# 16.net
KiCad netlist of a schematic drawn in Altium Designer
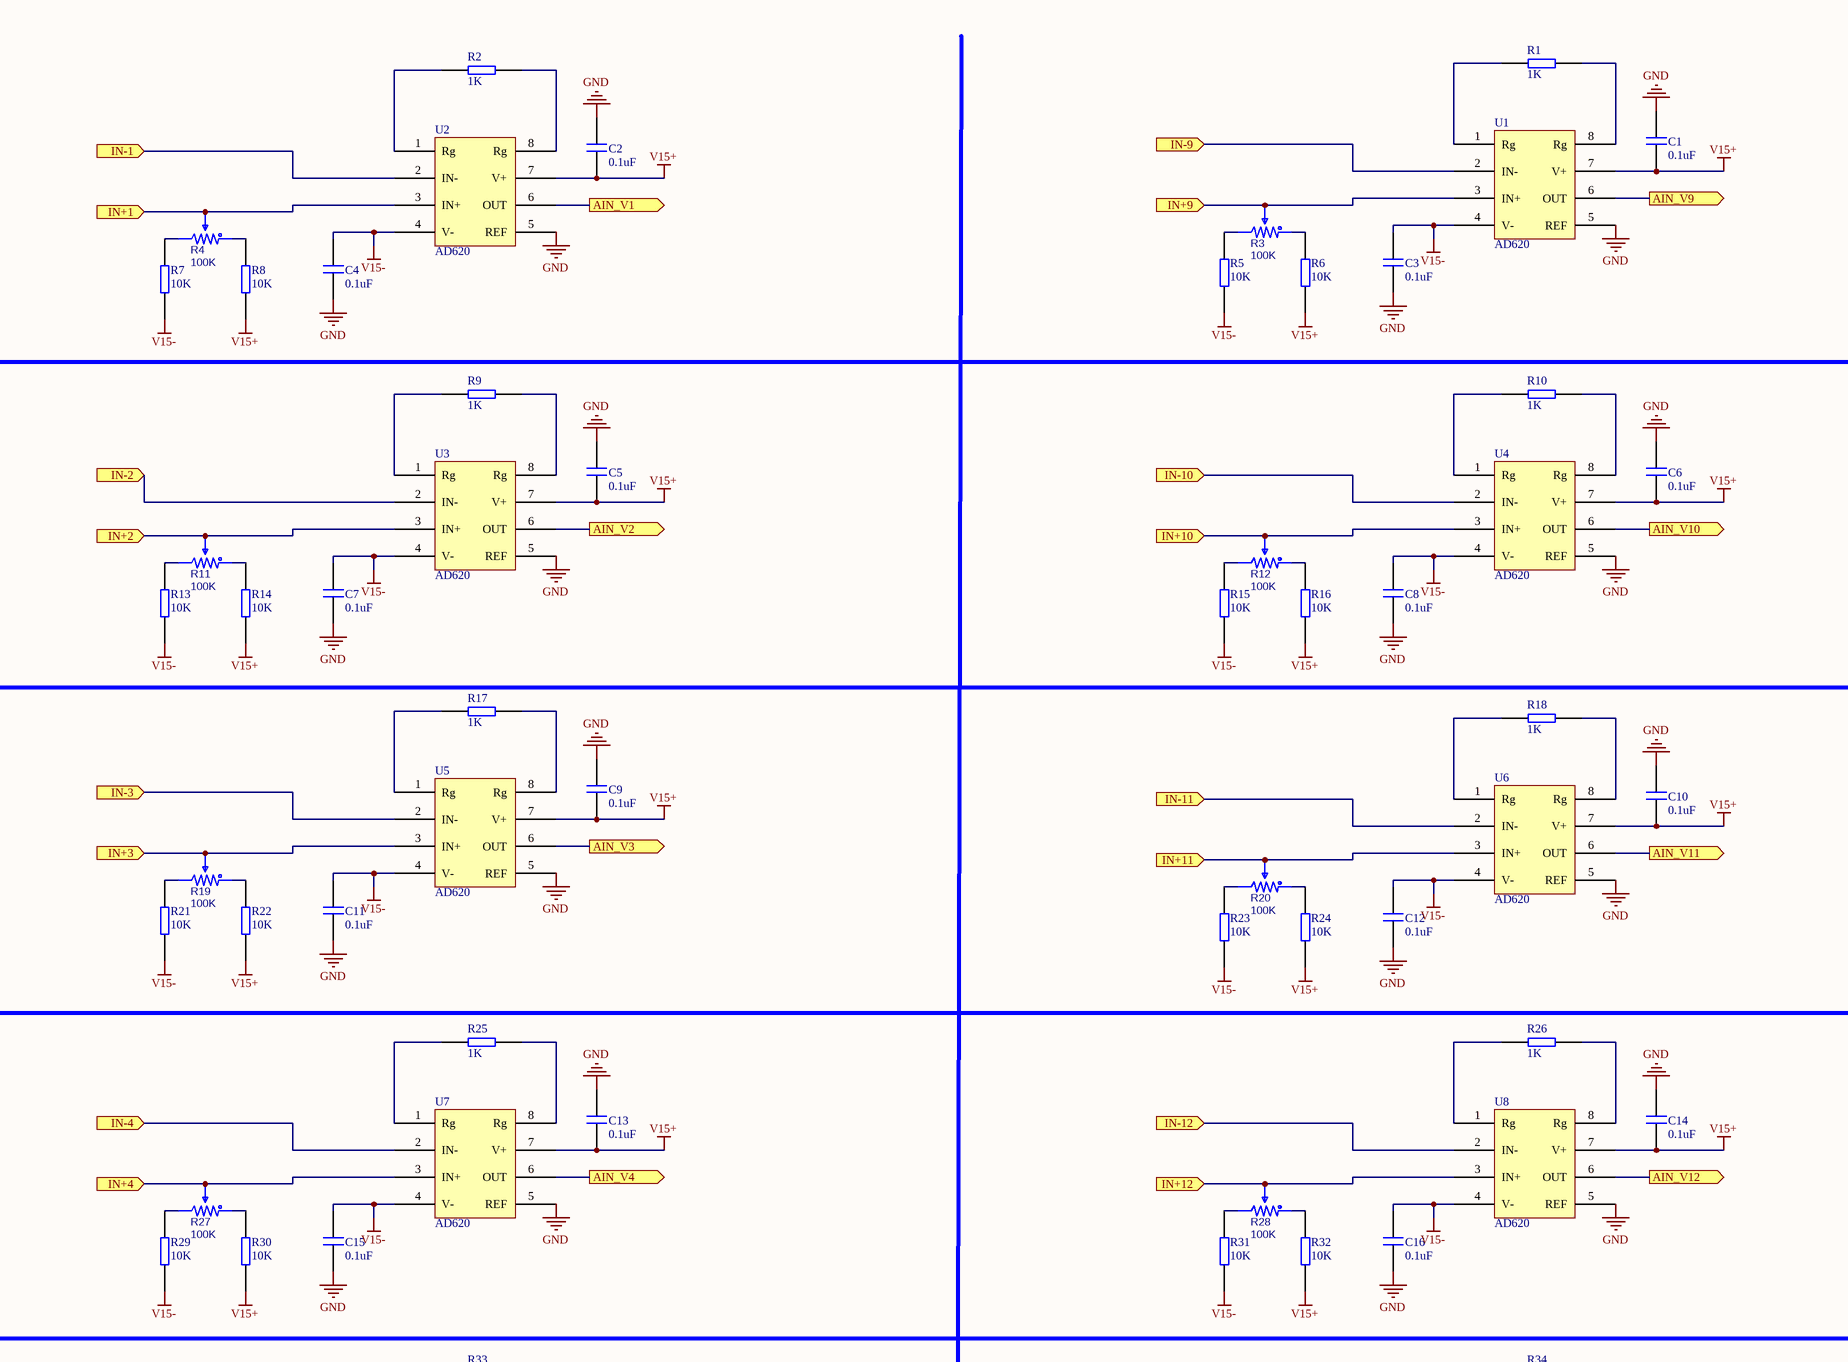
[diagram p0: 16路放大模块.SchDoc, top]
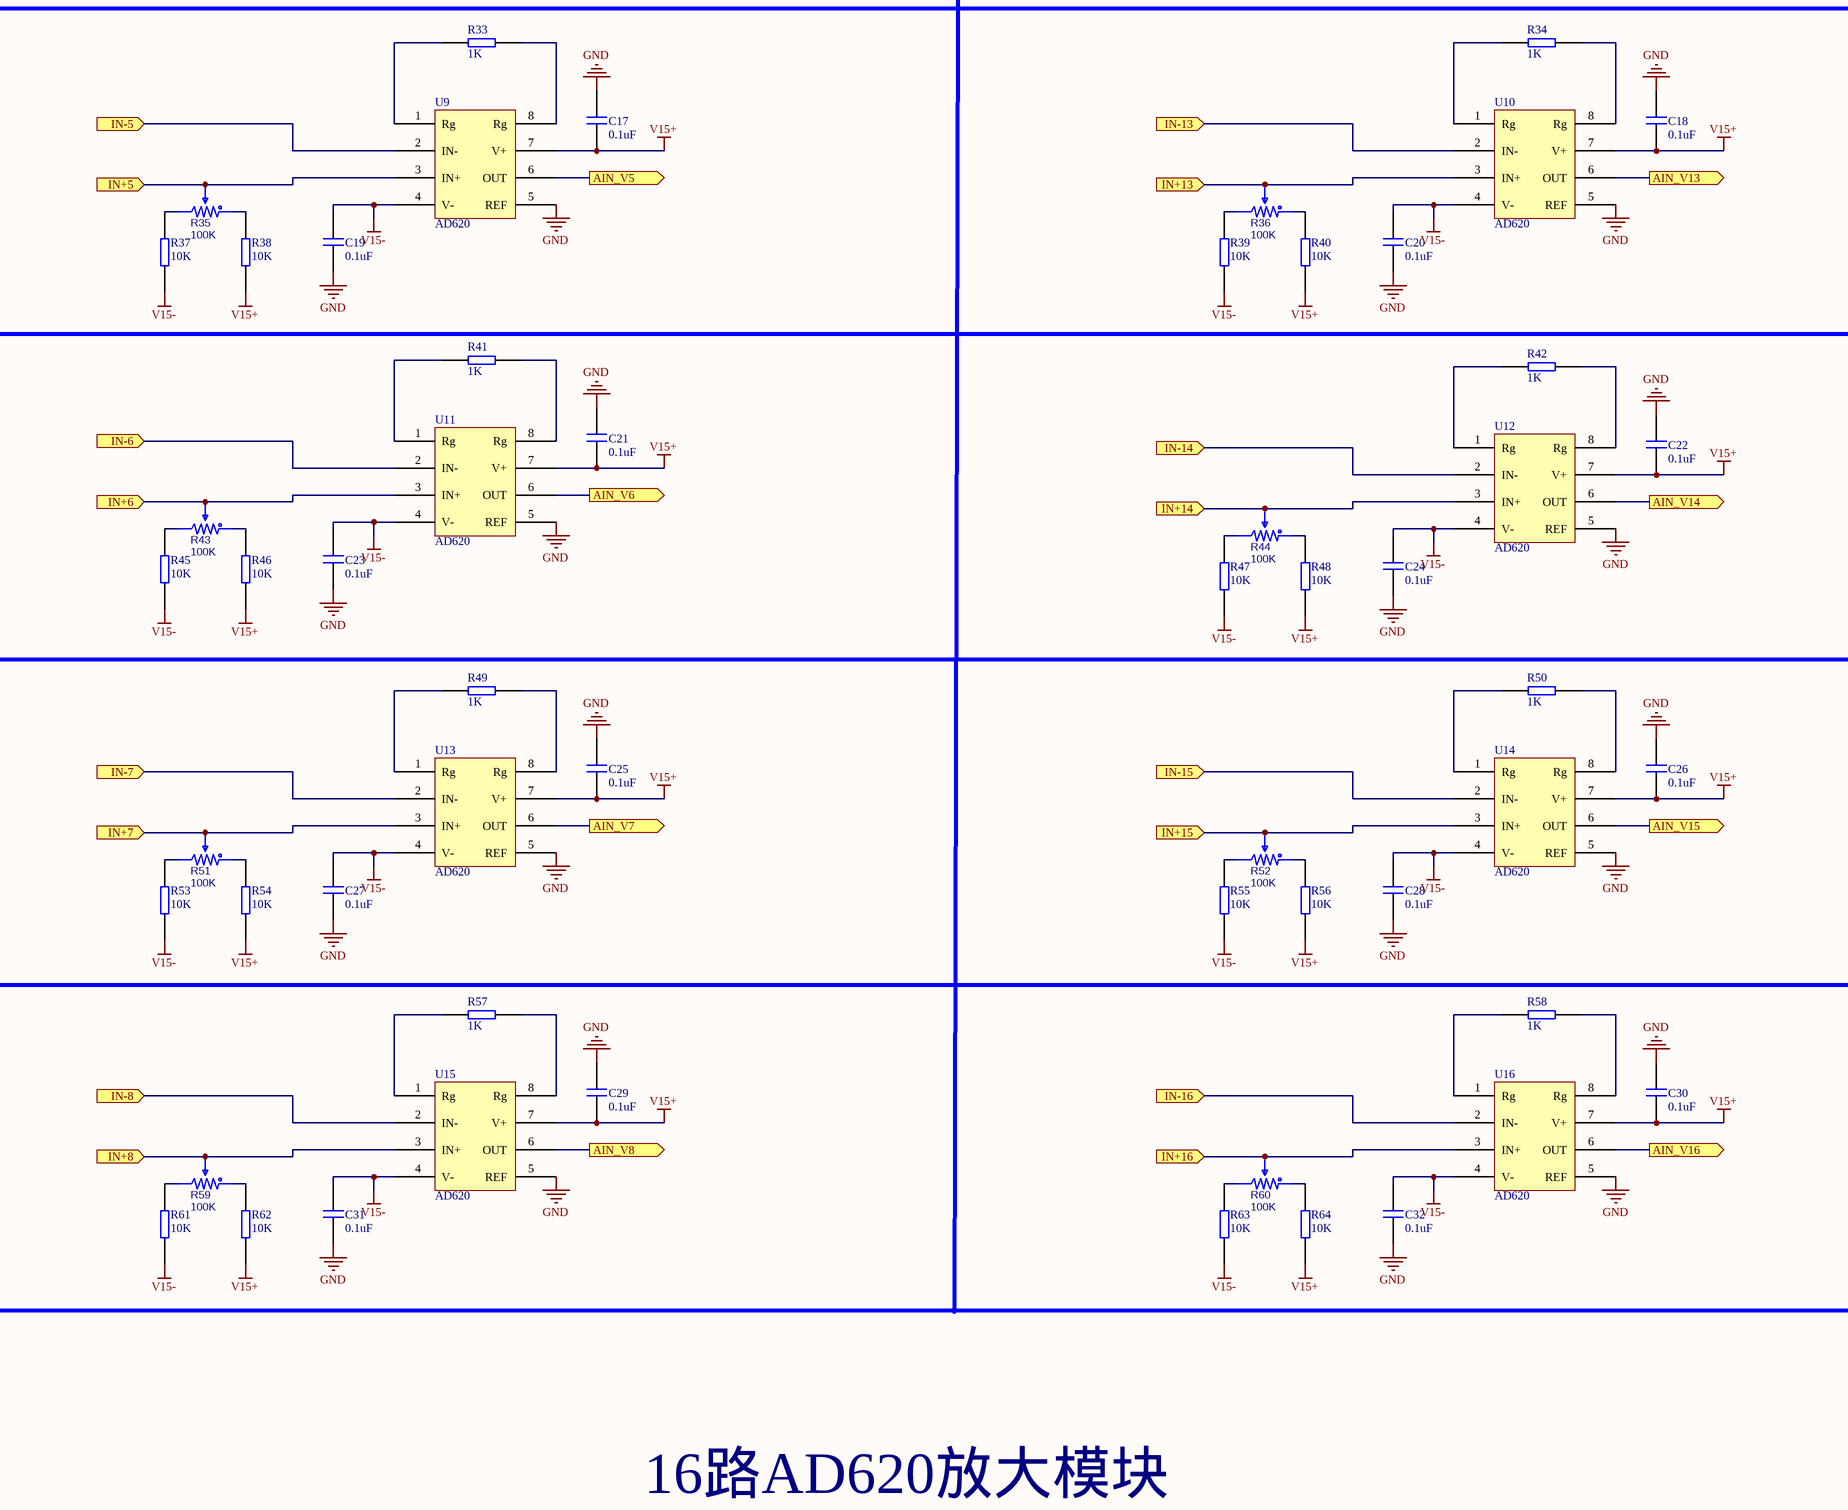
[diagram p1: 16路放大模块.SchDoc, bottom]

(export (version "E")
  (design (tool "Eeschema 10.0.6"))
  (components
    (comp (ref "C1")
      (value "0.1uF")
      (footprint "0805C")
      (description "普通电容")
      (libsource (lib "毕业设计") (part "CAP"))
    )
    (comp (ref "C2")
      (value "0.1uF")
      (footprint "0805C")
      (description "普通电容")
      (libsource (lib "毕业设计") (part "CAP"))
    )
    (comp (ref "C3")
      (value "0.1uF")
      (footprint "0805C")
      (description "普通电容")
      (libsource (lib "毕业设计") (part "CAP"))
    )
    (comp (ref "C4")
      (value "0.1uF")
      (footprint "0805C")
      (description "普通电容")
      (libsource (lib "毕业设计") (part "CAP"))
    )
    (comp (ref "C5")
      (value "0.1uF")
      (footprint "0805C")
      (description "普通电容")
      (libsource (lib "毕业设计") (part "CAP"))
    )
    (comp (ref "C6")
      (value "0.1uF")
      (footprint "0805C")
      (description "普通电容")
      (libsource (lib "毕业设计") (part "CAP"))
    )
    (comp (ref "C7")
      (value "0.1uF")
      (footprint "0805C")
      (description "普通电容")
      (libsource (lib "毕业设计") (part "CAP"))
    )
    (comp (ref "C8")
      (value "0.1uF")
      (footprint "0805C")
      (description "普通电容")
      (libsource (lib "毕业设计") (part "CAP"))
    )
    (comp (ref "C9")
      (value "0.1uF")
      (footprint "0805C")
      (description "普通电容")
      (libsource (lib "毕业设计") (part "CAP"))
    )
    (comp (ref "C10")
      (value "0.1uF")
      (footprint "0805C")
      (description "普通电容")
      (libsource (lib "毕业设计") (part "CAP"))
    )
    (comp (ref "C11")
      (value "0.1uF")
      (footprint "0805C")
      (description "普通电容")
      (libsource (lib "毕业设计") (part "CAP"))
    )
    (comp (ref "C12")
      (value "0.1uF")
      (footprint "0805C")
      (description "普通电容")
      (libsource (lib "毕业设计") (part "CAP"))
    )
    (comp (ref "C13")
      (value "0.1uF")
      (footprint "0805C")
      (description "普通电容")
      (libsource (lib "毕业设计") (part "CAP"))
    )
    (comp (ref "C14")
      (value "0.1uF")
      (footprint "0805C")
      (description "普通电容")
      (libsource (lib "毕业设计") (part "CAP"))
    )
    (comp (ref "C15")
      (value "0.1uF")
      (footprint "0805C")
      (description "普通电容")
      (libsource (lib "毕业设计") (part "CAP"))
    )
    (comp (ref "C16")
      (value "0.1uF")
      (footprint "0805C")
      (description "普通电容")
      (libsource (lib "毕业设计") (part "CAP"))
    )
    (comp (ref "C17")
      (value "0.1uF")
      (footprint "0805C")
      (description "普通电容")
      (libsource (lib "毕业设计") (part "CAP"))
    )
    (comp (ref "C18")
      (value "0.1uF")
      (footprint "0805C")
      (description "普通电容")
      (libsource (lib "毕业设计") (part "CAP"))
    )
    (comp (ref "C19")
      (value "0.1uF")
      (footprint "0805C")
      (description "普通电容")
      (libsource (lib "毕业设计") (part "CAP"))
    )
    (comp (ref "C20")
      (value "0.1uF")
      (footprint "0805C")
      (description "普通电容")
      (libsource (lib "毕业设计") (part "CAP"))
    )
    (comp (ref "C21")
      (value "0.1uF")
      (footprint "0805C")
      (description "普通电容")
      (libsource (lib "毕业设计") (part "CAP"))
    )
    (comp (ref "C22")
      (value "0.1uF")
      (footprint "0805C")
      (description "普通电容")
      (libsource (lib "毕业设计") (part "CAP"))
    )
    (comp (ref "C23")
      (value "0.1uF")
      (footprint "0805C")
      (description "普通电容")
      (libsource (lib "毕业设计") (part "CAP"))
    )
    (comp (ref "C24")
      (value "0.1uF")
      (footprint "0805C")
      (description "普通电容")
      (libsource (lib "毕业设计") (part "CAP"))
    )
    (comp (ref "C25")
      (value "0.1uF")
      (footprint "0805C")
      (description "普通电容")
      (libsource (lib "毕业设计") (part "CAP"))
    )
    (comp (ref "C26")
      (value "0.1uF")
      (footprint "0805C")
      (description "普通电容")
      (libsource (lib "毕业设计") (part "CAP"))
    )
    (comp (ref "C27")
      (value "0.1uF")
      (footprint "0805C")
      (description "普通电容")
      (libsource (lib "毕业设计") (part "CAP"))
    )
    (comp (ref "C28")
      (value "0.1uF")
      (footprint "0805C")
      (description "普通电容")
      (libsource (lib "毕业设计") (part "CAP"))
    )
    (comp (ref "C29")
      (value "0.1uF")
      (footprint "0805C")
      (description "普通电容")
      (libsource (lib "毕业设计") (part "CAP"))
    )
    (comp (ref "C30")
      (value "0.1uF")
      (footprint "0805C")
      (description "普通电容")
      (libsource (lib "毕业设计") (part "CAP"))
    )
    (comp (ref "C31")
      (value "0.1uF")
      (footprint "0805C")
      (description "普通电容")
      (libsource (lib "毕业设计") (part "CAP"))
    )
    (comp (ref "C32")
      (value "0.1uF")
      (footprint "0805C")
      (description "普通电容")
      (libsource (lib "毕业设计") (part "CAP"))
    )
    (comp (ref "R1")
      (value "1K")
      (footprint "0805R")
      (description "电阻模型")
      (libsource (lib "毕业设计") (part "RES"))
    )
    (comp (ref "R2")
      (value "1K")
      (footprint "0805R")
      (description "电阻模型")
      (libsource (lib "毕业设计") (part "RES"))
    )
    (comp (ref "R3")
      (value "100K")
      (footprint "RES-ADJ-SMD_G43BT")
      (description "电位器")
      (fields
        (field (name "BOM_SUPPLIER PART") "C125003")
        (field (name "BOM_MANUFACTURER PART") "3323P-1-104")
        (field (name "CONTRIBUTOR") "LCSC")
      )
      (libsource (lib "毕业设计") (part "100K"))
    )
    (comp (ref "R4")
      (value "100K")
      (footprint "RES-ADJ-SMD_G43BT")
      (description "电位器")
      (fields
        (field (name "BOM_SUPPLIER PART") "C125003")
        (field (name "BOM_MANUFACTURER PART") "3323P-1-104")
        (field (name "CONTRIBUTOR") "LCSC")
      )
      (libsource (lib "毕业设计") (part "100K"))
    )
    (comp (ref "R5")
      (value "10K")
      (footprint "0603R")
      (description "电阻模型")
      (libsource (lib "毕业设计") (part "RES"))
    )
    (comp (ref "R6")
      (value "10K")
      (footprint "0603R")
      (description "电阻模型")
      (libsource (lib "毕业设计") (part "RES"))
    )
    (comp (ref "R7")
      (value "10K")
      (footprint "0603R")
      (description "电阻模型")
      (libsource (lib "毕业设计") (part "RES"))
    )
    (comp (ref "R8")
      (value "10K")
      (footprint "0603R")
      (description "电阻模型")
      (libsource (lib "毕业设计") (part "RES"))
    )
    (comp (ref "R9")
      (value "1K")
      (footprint "0805R")
      (description "电阻模型")
      (libsource (lib "毕业设计") (part "RES"))
    )
    (comp (ref "R10")
      (value "1K")
      (footprint "0805R")
      (description "电阻模型")
      (libsource (lib "毕业设计") (part "RES"))
    )
    (comp (ref "R11")
      (value "100K")
      (footprint "RES-ADJ-SMD_G43BT")
      (description "电位器")
      (fields
        (field (name "BOM_SUPPLIER PART") "C125003")
        (field (name "BOM_MANUFACTURER PART") "3323P-1-104")
        (field (name "CONTRIBUTOR") "LCSC")
      )
      (libsource (lib "毕业设计") (part "100K"))
    )
    (comp (ref "R12")
      (value "100K")
      (footprint "RES-ADJ-SMD_G43BT")
      (description "电位器")
      (fields
        (field (name "BOM_SUPPLIER PART") "C125003")
        (field (name "BOM_MANUFACTURER PART") "3323P-1-104")
        (field (name "CONTRIBUTOR") "LCSC")
      )
      (libsource (lib "毕业设计") (part "100K"))
    )
    (comp (ref "R13")
      (value "10K")
      (footprint "0603R")
      (description "电阻模型")
      (libsource (lib "毕业设计") (part "RES"))
    )
    (comp (ref "R14")
      (value "10K")
      (footprint "0603R")
      (description "电阻模型")
      (libsource (lib "毕业设计") (part "RES"))
    )
    (comp (ref "R15")
      (value "10K")
      (footprint "0603R")
      (description "电阻模型")
      (libsource (lib "毕业设计") (part "RES"))
    )
    (comp (ref "R16")
      (value "10K")
      (footprint "0603R")
      (description "电阻模型")
      (libsource (lib "毕业设计") (part "RES"))
    )
    (comp (ref "R17")
      (value "1K")
      (footprint "0805R")
      (description "电阻模型")
      (libsource (lib "毕业设计") (part "RES"))
    )
    (comp (ref "R18")
      (value "1K")
      (footprint "0805R")
      (description "电阻模型")
      (libsource (lib "毕业设计") (part "RES"))
    )
    (comp (ref "R19")
      (value "100K")
      (footprint "RES-ADJ-SMD_G43BT")
      (description "电位器")
      (fields
        (field (name "BOM_SUPPLIER PART") "C125003")
        (field (name "BOM_MANUFACTURER PART") "3323P-1-104")
        (field (name "CONTRIBUTOR") "LCSC")
      )
      (libsource (lib "毕业设计") (part "100K"))
    )
    (comp (ref "R20")
      (value "100K")
      (footprint "RES-ADJ-SMD_G43BT")
      (description "电位器")
      (fields
        (field (name "BOM_SUPPLIER PART") "C125003")
        (field (name "BOM_MANUFACTURER PART") "3323P-1-104")
        (field (name "CONTRIBUTOR") "LCSC")
      )
      (libsource (lib "毕业设计") (part "100K"))
    )
    (comp (ref "R21")
      (value "10K")
      (footprint "0603R")
      (description "电阻模型")
      (libsource (lib "毕业设计") (part "RES"))
    )
    (comp (ref "R22")
      (value "10K")
      (footprint "0603R")
      (description "电阻模型")
      (libsource (lib "毕业设计") (part "RES"))
    )
    (comp (ref "R23")
      (value "10K")
      (footprint "0603R")
      (description "电阻模型")
      (libsource (lib "毕业设计") (part "RES"))
    )
    (comp (ref "R24")
      (value "10K")
      (footprint "0603R")
      (description "电阻模型")
      (libsource (lib "毕业设计") (part "RES"))
    )
    (comp (ref "R25")
      (value "1K")
      (footprint "0805R")
      (description "电阻模型")
      (libsource (lib "毕业设计") (part "RES"))
    )
    (comp (ref "R26")
      (value "1K")
      (footprint "0805R")
      (description "电阻模型")
      (libsource (lib "毕业设计") (part "RES"))
    )
    (comp (ref "R27")
      (value "100K")
      (footprint "RES-ADJ-SMD_G43BT")
      (description "电位器")
      (fields
        (field (name "BOM_SUPPLIER PART") "C125003")
        (field (name "BOM_MANUFACTURER PART") "3323P-1-104")
        (field (name "CONTRIBUTOR") "LCSC")
      )
      (libsource (lib "毕业设计") (part "100K"))
    )
    (comp (ref "R28")
      (value "100K")
      (footprint "RES-ADJ-SMD_G43BT")
      (description "电位器")
      (fields
        (field (name "BOM_SUPPLIER PART") "C125003")
        (field (name "BOM_MANUFACTURER PART") "3323P-1-104")
        (field (name "CONTRIBUTOR") "LCSC")
      )
      (libsource (lib "毕业设计") (part "100K"))
    )
    (comp (ref "R29")
      (value "10K")
      (footprint "0603R")
      (description "电阻模型")
      (libsource (lib "毕业设计") (part "RES"))
    )
    (comp (ref "R30")
      (value "10K")
      (footprint "0603R")
      (description "电阻模型")
      (libsource (lib "毕业设计") (part "RES"))
    )
    (comp (ref "R31")
      (value "10K")
      (footprint "0603R")
      (description "电阻模型")
      (libsource (lib "毕业设计") (part "RES"))
    )
    (comp (ref "R32")
      (value "10K")
      (footprint "0603R")
      (description "电阻模型")
      (libsource (lib "毕业设计") (part "RES"))
    )
    (comp (ref "R33")
      (value "1K")
      (footprint "0805R")
      (description "电阻模型")
      (libsource (lib "毕业设计") (part "RES"))
    )
    (comp (ref "R34")
      (value "1K")
      (footprint "0805R")
      (description "电阻模型")
      (libsource (lib "毕业设计") (part "RES"))
    )
    (comp (ref "R35")
      (value "100K")
      (footprint "RES-ADJ-SMD_G43BT")
      (description "电位器")
      (fields
        (field (name "BOM_SUPPLIER PART") "C125003")
        (field (name "BOM_MANUFACTURER PART") "3323P-1-104")
        (field (name "CONTRIBUTOR") "LCSC")
      )
      (libsource (lib "毕业设计") (part "100K"))
    )
    (comp (ref "R36")
      (value "100K")
      (footprint "RES-ADJ-SMD_G43BT")
      (description "电位器")
      (fields
        (field (name "BOM_SUPPLIER PART") "C125003")
        (field (name "BOM_MANUFACTURER PART") "3323P-1-104")
        (field (name "CONTRIBUTOR") "LCSC")
      )
      (libsource (lib "毕业设计") (part "100K"))
    )
    (comp (ref "R37")
      (value "10K")
      (footprint "0603R")
      (description "电阻模型")
      (libsource (lib "毕业设计") (part "RES"))
    )
    (comp (ref "R38")
      (value "10K")
      (footprint "0603R")
      (description "电阻模型")
      (libsource (lib "毕业设计") (part "RES"))
    )
    (comp (ref "R39")
      (value "10K")
      (footprint "0603R")
      (description "电阻模型")
      (libsource (lib "毕业设计") (part "RES"))
    )
    (comp (ref "R40")
      (value "10K")
      (footprint "0603R")
      (description "电阻模型")
      (libsource (lib "毕业设计") (part "RES"))
    )
    (comp (ref "R41")
      (value "1K")
      (footprint "0805R")
      (description "电阻模型")
      (libsource (lib "毕业设计") (part "RES"))
    )
    (comp (ref "R42")
      (value "1K")
      (footprint "0805R")
      (description "电阻模型")
      (libsource (lib "毕业设计") (part "RES"))
    )
    (comp (ref "R43")
      (value "100K")
      (footprint "RES-ADJ-SMD_G43BT")
      (description "电位器")
      (fields
        (field (name "BOM_SUPPLIER PART") "C125003")
        (field (name "BOM_MANUFACTURER PART") "3323P-1-104")
        (field (name "CONTRIBUTOR") "LCSC")
      )
      (libsource (lib "毕业设计") (part "100K"))
    )
    (comp (ref "R44")
      (value "100K")
      (footprint "RES-ADJ-SMD_G43BT")
      (description "电位器")
      (fields
        (field (name "BOM_SUPPLIER PART") "C125003")
        (field (name "BOM_MANUFACTURER PART") "3323P-1-104")
        (field (name "CONTRIBUTOR") "LCSC")
      )
      (libsource (lib "毕业设计") (part "100K"))
    )
    (comp (ref "R45")
      (value "10K")
      (footprint "0603R")
      (description "电阻模型")
      (libsource (lib "毕业设计") (part "RES"))
    )
    (comp (ref "R46")
      (value "10K")
      (footprint "0603R")
      (description "电阻模型")
      (libsource (lib "毕业设计") (part "RES"))
    )
    (comp (ref "R47")
      (value "10K")
      (footprint "0603R")
      (description "电阻模型")
      (libsource (lib "毕业设计") (part "RES"))
    )
    (comp (ref "R48")
      (value "10K")
      (footprint "0603R")
      (description "电阻模型")
      (libsource (lib "毕业设计") (part "RES"))
    )
    (comp (ref "R49")
      (value "1K")
      (footprint "0805R")
      (description "电阻模型")
      (libsource (lib "毕业设计") (part "RES"))
    )
    (comp (ref "R50")
      (value "1K")
      (footprint "0805R")
      (description "电阻模型")
      (libsource (lib "毕业设计") (part "RES"))
    )
    (comp (ref "R51")
      (value "100K")
      (footprint "RES-ADJ-SMD_G43BT")
      (description "电位器")
      (fields
        (field (name "BOM_SUPPLIER PART") "C125003")
        (field (name "BOM_MANUFACTURER PART") "3323P-1-104")
        (field (name "CONTRIBUTOR") "LCSC")
      )
      (libsource (lib "毕业设计") (part "100K"))
    )
    (comp (ref "R52")
      (value "100K")
      (footprint "RES-ADJ-SMD_G43BT")
      (description "电位器")
      (fields
        (field (name "BOM_SUPPLIER PART") "C125003")
        (field (name "BOM_MANUFACTURER PART") "3323P-1-104")
        (field (name "CONTRIBUTOR") "LCSC")
      )
      (libsource (lib "毕业设计") (part "100K"))
    )
    (comp (ref "R53")
      (value "10K")
      (footprint "0603R")
      (description "电阻模型")
      (libsource (lib "毕业设计") (part "RES"))
    )
    (comp (ref "R54")
      (value "10K")
      (footprint "0603R")
      (description "电阻模型")
      (libsource (lib "毕业设计") (part "RES"))
    )
    (comp (ref "R55")
      (value "10K")
      (footprint "0603R")
      (description "电阻模型")
      (libsource (lib "毕业设计") (part "RES"))
    )
    (comp (ref "R56")
      (value "10K")
      (footprint "0603R")
      (description "电阻模型")
      (libsource (lib "毕业设计") (part "RES"))
    )
    (comp (ref "R57")
      (value "1K")
      (footprint "0805R")
      (description "电阻模型")
      (libsource (lib "毕业设计") (part "RES"))
    )
    (comp (ref "R58")
      (value "1K")
      (footprint "0805R")
      (description "电阻模型")
      (libsource (lib "毕业设计") (part "RES"))
    )
    (comp (ref "R59")
      (value "100K")
      (footprint "RES-ADJ-SMD_G43BT")
      (description "电位器")
      (fields
        (field (name "BOM_SUPPLIER PART") "C125003")
        (field (name "BOM_MANUFACTURER PART") "3323P-1-104")
        (field (name "CONTRIBUTOR") "LCSC")
      )
      (libsource (lib "毕业设计") (part "100K"))
    )
    (comp (ref "R60")
      (value "100K")
      (footprint "RES-ADJ-SMD_G43BT")
      (description "电位器")
      (fields
        (field (name "BOM_SUPPLIER PART") "C125003")
        (field (name "BOM_MANUFACTURER PART") "3323P-1-104")
        (field (name "CONTRIBUTOR") "LCSC")
      )
      (libsource (lib "毕业设计") (part "100K"))
    )
    (comp (ref "R61")
      (value "10K")
      (footprint "0603R")
      (description "电阻模型")
      (libsource (lib "毕业设计") (part "RES"))
    )
    (comp (ref "R62")
      (value "10K")
      (footprint "0603R")
      (description "电阻模型")
      (libsource (lib "毕业设计") (part "RES"))
    )
    (comp (ref "R63")
      (value "10K")
      (footprint "0603R")
      (description "电阻模型")
      (libsource (lib "毕业设计") (part "RES"))
    )
    (comp (ref "R64")
      (value "10K")
      (footprint "0603R")
      (description "电阻模型")
      (libsource (lib "毕业设计") (part "RES"))
    )
    (comp (ref "U1")
      (value "AD620")
      (footprint "SOIC127P600X175-8N")
      (description "仪表放大芯片")
      (libsource (lib "毕业设计") (part "AD620"))
    )
    (comp (ref "U2")
      (value "AD620")
      (footprint "SOIC127P600X175-8N")
      (description "仪表放大芯片")
      (libsource (lib "毕业设计") (part "AD620"))
    )
    (comp (ref "U3")
      (value "AD620")
      (footprint "SOIC127P600X175-8N")
      (description "仪表放大芯片")
      (libsource (lib "毕业设计") (part "AD620"))
    )
    (comp (ref "U4")
      (value "AD620")
      (footprint "SOIC127P600X175-8N")
      (description "仪表放大芯片")
      (libsource (lib "毕业设计") (part "AD620"))
    )
    (comp (ref "U5")
      (value "AD620")
      (footprint "SOIC127P600X175-8N")
      (description "仪表放大芯片")
      (libsource (lib "毕业设计") (part "AD620"))
    )
    (comp (ref "U6")
      (value "AD620")
      (footprint "SOIC127P600X175-8N")
      (description "仪表放大芯片")
      (libsource (lib "毕业设计") (part "AD620"))
    )
    (comp (ref "U7")
      (value "AD620")
      (footprint "SOIC127P600X175-8N")
      (description "仪表放大芯片")
      (libsource (lib "毕业设计") (part "AD620"))
    )
    (comp (ref "U8")
      (value "AD620")
      (footprint "SOIC127P600X175-8N")
      (description "仪表放大芯片")
      (libsource (lib "毕业设计") (part "AD620"))
    )
    (comp (ref "U9")
      (value "AD620")
      (footprint "SOIC127P600X175-8N")
      (description "仪表放大芯片")
      (libsource (lib "毕业设计") (part "AD620"))
    )
    (comp (ref "U10")
      (value "AD620")
      (footprint "SOIC127P600X175-8N")
      (description "仪表放大芯片")
      (libsource (lib "毕业设计") (part "AD620"))
    )
    (comp (ref "U11")
      (value "AD620")
      (footprint "SOIC127P600X175-8N")
      (description "仪表放大芯片")
      (libsource (lib "毕业设计") (part "AD620"))
    )
    (comp (ref "U12")
      (value "AD620")
      (footprint "SOIC127P600X175-8N")
      (description "仪表放大芯片")
      (libsource (lib "毕业设计") (part "AD620"))
    )
    (comp (ref "U13")
      (value "AD620")
      (footprint "SOIC127P600X175-8N")
      (description "仪表放大芯片")
      (libsource (lib "毕业设计") (part "AD620"))
    )
    (comp (ref "U14")
      (value "AD620")
      (footprint "SOIC127P600X175-8N")
      (description "仪表放大芯片")
      (libsource (lib "毕业设计") (part "AD620"))
    )
    (comp (ref "U15")
      (value "AD620")
      (footprint "SOIC127P600X175-8N")
      (description "仪表放大芯片")
      (libsource (lib "毕业设计") (part "AD620"))
    )
    (comp (ref "U16")
      (value "AD620")
      (footprint "SOIC127P600X175-8N")
      (description "仪表放大芯片")
      (libsource (lib "毕业设计") (part "AD620"))
    )
  )
  (nets
    (net (code "1") (name "/AIN_V1") (class "Default")
      (node (ref "U2") (pin "6") (pinfunction "OUT_6") (pintype "passive"))
    )
    (net (code "2") (name "/AIN_V2") (class "Default")
      (node (ref "U3") (pin "6") (pinfunction "OUT_6") (pintype "passive"))
    )
    (net (code "3") (name "/AIN_V3") (class "Default")
      (node (ref "U5") (pin "6") (pinfunction "OUT_6") (pintype "passive"))
    )
    (net (code "4") (name "/AIN_V4") (class "Default")
      (node (ref "U7") (pin "6") (pinfunction "OUT_6") (pintype "passive"))
    )
    (net (code "5") (name "/AIN_V5") (class "Default")
      (node (ref "U9") (pin "6") (pinfunction "OUT_6") (pintype "passive"))
    )
    (net (code "6") (name "/AIN_V6") (class "Default")
      (node (ref "U11") (pin "6") (pinfunction "OUT_6") (pintype "passive"))
    )
    (net (code "7") (name "/AIN_V7") (class "Default")
      (node (ref "U13") (pin "6") (pinfunction "OUT_6") (pintype "passive"))
    )
    (net (code "8") (name "/AIN_V8") (class "Default")
      (node (ref "U15") (pin "6") (pinfunction "OUT_6") (pintype "passive"))
    )
    (net (code "9") (name "/AIN_V9") (class "Default")
      (node (ref "U1") (pin "6") (pinfunction "OUT_6") (pintype "passive"))
    )
    (net (code "10") (name "/AIN_V10") (class "Default")
      (node (ref "U4") (pin "6") (pinfunction "OUT_6") (pintype "passive"))
    )
    (net (code "11") (name "/AIN_V11") (class "Default")
      (node (ref "U6") (pin "6") (pinfunction "OUT_6") (pintype "passive"))
    )
    (net (code "12") (name "/AIN_V12") (class "Default")
      (node (ref "U8") (pin "6") (pinfunction "OUT_6") (pintype "passive"))
    )
    (net (code "13") (name "/AIN_V13") (class "Default")
      (node (ref "U10") (pin "6") (pinfunction "OUT_6") (pintype "passive"))
    )
    (net (code "14") (name "/AIN_V14") (class "Default")
      (node (ref "U12") (pin "6") (pinfunction "OUT_6") (pintype "passive"))
    )
    (net (code "15") (name "/AIN_V15") (class "Default")
      (node (ref "U14") (pin "6") (pinfunction "OUT_6") (pintype "passive"))
    )
    (net (code "16") (name "/AIN_V16") (class "Default")
      (node (ref "U16") (pin "6") (pinfunction "OUT_6") (pintype "passive"))
    )
    (net (code "17") (name "/IN+1") (class "Default")
      (node (ref "R4") (pin "2") (pinfunction "2_2") (pintype "passive"))
      (node (ref "U2") (pin "3") (pinfunction "IN+_3") (pintype "passive"))
    )
    (net (code "18") (name "/IN+2") (class "Default")
      (node (ref "R11") (pin "2") (pinfunction "2_2") (pintype "passive"))
      (node (ref "U3") (pin "3") (pinfunction "IN+_3") (pintype "passive"))
    )
    (net (code "19") (name "/IN+3") (class "Default")
      (node (ref "R19") (pin "2") (pinfunction "2_2") (pintype "passive"))
      (node (ref "U5") (pin "3") (pinfunction "IN+_3") (pintype "passive"))
    )
    (net (code "20") (name "/IN+4") (class "Default")
      (node (ref "R27") (pin "2") (pinfunction "2_2") (pintype "passive"))
      (node (ref "U7") (pin "3") (pinfunction "IN+_3") (pintype "passive"))
    )
    (net (code "21") (name "/IN+5") (class "Default")
      (node (ref "R35") (pin "2") (pinfunction "2_2") (pintype "passive"))
      (node (ref "U9") (pin "3") (pinfunction "IN+_3") (pintype "passive"))
    )
    (net (code "22") (name "/IN+6") (class "Default")
      (node (ref "R43") (pin "2") (pinfunction "2_2") (pintype "passive"))
      (node (ref "U11") (pin "3") (pinfunction "IN+_3") (pintype "passive"))
    )
    (net (code "23") (name "/IN+7") (class "Default")
      (node (ref "R51") (pin "2") (pinfunction "2_2") (pintype "passive"))
      (node (ref "U13") (pin "3") (pinfunction "IN+_3") (pintype "passive"))
    )
    (net (code "24") (name "/IN+8") (class "Default")
      (node (ref "R59") (pin "2") (pinfunction "2_2") (pintype "passive"))
      (node (ref "U15") (pin "3") (pinfunction "IN+_3") (pintype "passive"))
    )
    (net (code "25") (name "/IN+9") (class "Default")
      (node (ref "R3") (pin "2") (pinfunction "2_2") (pintype "passive"))
      (node (ref "U1") (pin "3") (pinfunction "IN+_3") (pintype "passive"))
    )
    (net (code "26") (name "/IN+10") (class "Default")
      (node (ref "R12") (pin "2") (pinfunction "2_2") (pintype "passive"))
      (node (ref "U4") (pin "3") (pinfunction "IN+_3") (pintype "passive"))
    )
    (net (code "27") (name "/IN+11") (class "Default")
      (node (ref "R20") (pin "2") (pinfunction "2_2") (pintype "passive"))
      (node (ref "U6") (pin "3") (pinfunction "IN+_3") (pintype "passive"))
    )
    (net (code "28") (name "/IN+12") (class "Default")
      (node (ref "R28") (pin "2") (pinfunction "2_2") (pintype "passive"))
      (node (ref "U8") (pin "3") (pinfunction "IN+_3") (pintype "passive"))
    )
    (net (code "29") (name "/IN+13") (class "Default")
      (node (ref "R36") (pin "2") (pinfunction "2_2") (pintype "passive"))
      (node (ref "U10") (pin "3") (pinfunction "IN+_3") (pintype "passive"))
    )
    (net (code "30") (name "/IN+14") (class "Default")
      (node (ref "R44") (pin "2") (pinfunction "2_2") (pintype "passive"))
      (node (ref "U12") (pin "3") (pinfunction "IN+_3") (pintype "passive"))
    )
    (net (code "31") (name "/IN+15") (class "Default")
      (node (ref "R52") (pin "2") (pinfunction "2_2") (pintype "passive"))
      (node (ref "U14") (pin "3") (pinfunction "IN+_3") (pintype "passive"))
    )
    (net (code "32") (name "/IN+16") (class "Default")
      (node (ref "R60") (pin "2") (pinfunction "2_2") (pintype "passive"))
      (node (ref "U16") (pin "3") (pinfunction "IN+_3") (pintype "passive"))
    )
    (net (code "33") (name "/IN-1") (class "Default")
      (node (ref "U2") (pin "2") (pinfunction "IN-_2") (pintype "passive"))
    )
    (net (code "34") (name "/IN-2") (class "Default")
      (node (ref "U3") (pin "2") (pinfunction "IN-_2") (pintype "passive"))
    )
    (net (code "35") (name "/IN-3") (class "Default")
      (node (ref "U5") (pin "2") (pinfunction "IN-_2") (pintype "passive"))
    )
    (net (code "36") (name "/IN-4") (class "Default")
      (node (ref "U7") (pin "2") (pinfunction "IN-_2") (pintype "passive"))
    )
    (net (code "37") (name "/IN-5") (class "Default")
      (node (ref "U9") (pin "2") (pinfunction "IN-_2") (pintype "passive"))
    )
    (net (code "38") (name "/IN-6") (class "Default")
      (node (ref "U11") (pin "2") (pinfunction "IN-_2") (pintype "passive"))
    )
    (net (code "39") (name "/IN-7") (class "Default")
      (node (ref "U13") (pin "2") (pinfunction "IN-_2") (pintype "passive"))
    )
    (net (code "40") (name "/IN-8") (class "Default")
      (node (ref "U15") (pin "2") (pinfunction "IN-_2") (pintype "passive"))
    )
    (net (code "41") (name "/IN-9") (class "Default")
      (node (ref "U1") (pin "2") (pinfunction "IN-_2") (pintype "passive"))
    )
    (net (code "42") (name "/IN-10") (class "Default")
      (node (ref "U4") (pin "2") (pinfunction "IN-_2") (pintype "passive"))
    )
    (net (code "43") (name "/IN-11") (class "Default")
      (node (ref "U6") (pin "2") (pinfunction "IN-_2") (pintype "passive"))
    )
    (net (code "44") (name "/IN-12") (class "Default")
      (node (ref "U8") (pin "2") (pinfunction "IN-_2") (pintype "passive"))
    )
    (net (code "45") (name "/IN-13") (class "Default")
      (node (ref "U10") (pin "2") (pinfunction "IN-_2") (pintype "passive"))
    )
    (net (code "46") (name "/IN-14") (class "Default")
      (node (ref "U12") (pin "2") (pinfunction "IN-_2") (pintype "passive"))
    )
    (net (code "47") (name "/IN-15") (class "Default")
      (node (ref "U14") (pin "2") (pinfunction "IN-_2") (pintype "passive"))
    )
    (net (code "48") (name "/IN-16") (class "Default")
      (node (ref "U16") (pin "2") (pinfunction "IN-_2") (pintype "passive"))
    )
    (net (code "49") (name "GND") (class "Default")
      (node (ref "C1") (pin "2") (pinfunction "2_2") (pintype "passive"))
      (node (ref "C10") (pin "2") (pinfunction "2_2") (pintype "passive"))
      (node (ref "C11") (pin "1") (pinfunction "1_1") (pintype "passive"))
      (node (ref "C12") (pin "1") (pinfunction "1_1") (pintype "passive"))
      (node (ref "C13") (pin "2") (pinfunction "2_2") (pintype "passive"))
      (node (ref "C14") (pin "2") (pinfunction "2_2") (pintype "passive"))
      (node (ref "C15") (pin "1") (pinfunction "1_1") (pintype "passive"))
      (node (ref "C16") (pin "1") (pinfunction "1_1") (pintype "passive"))
      (node (ref "C17") (pin "2") (pinfunction "2_2") (pintype "passive"))
      (node (ref "C18") (pin "2") (pinfunction "2_2") (pintype "passive"))
      (node (ref "C19") (pin "1") (pinfunction "1_1") (pintype "passive"))
      (node (ref "C2") (pin "2") (pinfunction "2_2") (pintype "passive"))
      (node (ref "C20") (pin "1") (pinfunction "1_1") (pintype "passive"))
      (node (ref "C21") (pin "2") (pinfunction "2_2") (pintype "passive"))
      (node (ref "C22") (pin "2") (pinfunction "2_2") (pintype "passive"))
      (node (ref "C23") (pin "1") (pinfunction "1_1") (pintype "passive"))
      (node (ref "C24") (pin "1") (pinfunction "1_1") (pintype "passive"))
      (node (ref "C25") (pin "2") (pinfunction "2_2") (pintype "passive"))
      (node (ref "C26") (pin "2") (pinfunction "2_2") (pintype "passive"))
      (node (ref "C27") (pin "1") (pinfunction "1_1") (pintype "passive"))
      (node (ref "C28") (pin "1") (pinfunction "1_1") (pintype "passive"))
      (node (ref "C29") (pin "2") (pinfunction "2_2") (pintype "passive"))
      (node (ref "C3") (pin "1") (pinfunction "1_1") (pintype "passive"))
      (node (ref "C30") (pin "2") (pinfunction "2_2") (pintype "passive"))
      (node (ref "C31") (pin "1") (pinfunction "1_1") (pintype "passive"))
      (node (ref "C32") (pin "1") (pinfunction "1_1") (pintype "passive"))
      (node (ref "C4") (pin "1") (pinfunction "1_1") (pintype "passive"))
      (node (ref "C5") (pin "2") (pinfunction "2_2") (pintype "passive"))
      (node (ref "C6") (pin "2") (pinfunction "2_2") (pintype "passive"))
      (node (ref "C7") (pin "1") (pinfunction "1_1") (pintype "passive"))
      (node (ref "C8") (pin "1") (pinfunction "1_1") (pintype "passive"))
      (node (ref "C9") (pin "2") (pinfunction "2_2") (pintype "passive"))
      (node (ref "U1") (pin "5") (pinfunction "REF_5") (pintype "passive"))
      (node (ref "U10") (pin "5") (pinfunction "REF_5") (pintype "passive"))
      (node (ref "U11") (pin "5") (pinfunction "REF_5") (pintype "passive"))
      (node (ref "U12") (pin "5") (pinfunction "REF_5") (pintype "passive"))
      (node (ref "U13") (pin "5") (pinfunction "REF_5") (pintype "passive"))
      (node (ref "U14") (pin "5") (pinfunction "REF_5") (pintype "passive"))
      (node (ref "U15") (pin "5") (pinfunction "REF_5") (pintype "passive"))
      (node (ref "U16") (pin "5") (pinfunction "REF_5") (pintype "passive"))
      (node (ref "U2") (pin "5") (pinfunction "REF_5") (pintype "passive"))
      (node (ref "U3") (pin "5") (pinfunction "REF_5") (pintype "passive"))
      (node (ref "U4") (pin "5") (pinfunction "REF_5") (pintype "passive"))
      (node (ref "U5") (pin "5") (pinfunction "REF_5") (pintype "passive"))
      (node (ref "U6") (pin "5") (pinfunction "REF_5") (pintype "passive"))
      (node (ref "U7") (pin "5") (pinfunction "REF_5") (pintype "passive"))
      (node (ref "U8") (pin "5") (pinfunction "REF_5") (pintype "passive"))
      (node (ref "U9") (pin "5") (pinfunction "REF_5") (pintype "passive"))
    )
    (net (code "50") (name "Net-(R1-Pad1)") (class "Default")
      (node (ref "R1") (pin "1") (pinfunction "1_1") (pintype "passive"))
      (node (ref "U1") (pin "1") (pinfunction "Rg_1") (pintype "passive"))
    )
    (net (code "51") (name "Net-(R1-Pad2)") (class "Default")
      (node (ref "R1") (pin "2") (pinfunction "2_2") (pintype "passive"))
      (node (ref "U1") (pin "8") (pinfunction "Rg_8") (pintype "passive"))
    )
    (net (code "52") (name "Net-(R2-Pad1)") (class "Default")
      (node (ref "R2") (pin "1") (pinfunction "1_1") (pintype "passive"))
      (node (ref "U2") (pin "1") (pinfunction "Rg_1") (pintype "passive"))
    )
    (net (code "53") (name "Net-(R2-Pad2)") (class "Default")
      (node (ref "R2") (pin "2") (pinfunction "2_2") (pintype "passive"))
      (node (ref "U2") (pin "8") (pinfunction "Rg_8") (pintype "passive"))
    )
    (net (code "54") (name "Net-(R3-Pad1)") (class "Default")
      (node (ref "R3") (pin "1") (pinfunction "1_1") (pintype "passive"))
      (node (ref "R6") (pin "2") (pinfunction "2_2") (pintype "passive"))
    )
    (net (code "55") (name "Net-(R3-Pad3)") (class "Default")
      (node (ref "R3") (pin "3") (pinfunction "3_3") (pintype "passive"))
      (node (ref "R5") (pin "2") (pinfunction "2_2") (pintype "passive"))
    )
    (net (code "56") (name "Net-(R4-Pad1)") (class "Default")
      (node (ref "R4") (pin "1") (pinfunction "1_1") (pintype "passive"))
      (node (ref "R8") (pin "2") (pinfunction "2_2") (pintype "passive"))
    )
    (net (code "57") (name "Net-(R4-Pad3)") (class "Default")
      (node (ref "R4") (pin "3") (pinfunction "3_3") (pintype "passive"))
      (node (ref "R7") (pin "2") (pinfunction "2_2") (pintype "passive"))
    )
    (net (code "58") (name "Net-(R9-Pad1)") (class "Default")
      (node (ref "R9") (pin "1") (pinfunction "1_1") (pintype "passive"))
      (node (ref "U3") (pin "1") (pinfunction "Rg_1") (pintype "passive"))
    )
    (net (code "59") (name "Net-(R9-Pad2)") (class "Default")
      (node (ref "R9") (pin "2") (pinfunction "2_2") (pintype "passive"))
      (node (ref "U3") (pin "8") (pinfunction "Rg_8") (pintype "passive"))
    )
    (net (code "60") (name "Net-(R10-Pad1)") (class "Default")
      (node (ref "R10") (pin "1") (pinfunction "1_1") (pintype "passive"))
      (node (ref "U4") (pin "1") (pinfunction "Rg_1") (pintype "passive"))
    )
    (net (code "61") (name "Net-(R10-Pad2)") (class "Default")
      (node (ref "R10") (pin "2") (pinfunction "2_2") (pintype "passive"))
      (node (ref "U4") (pin "8") (pinfunction "Rg_8") (pintype "passive"))
    )
    (net (code "62") (name "Net-(R11-Pad1)") (class "Default")
      (node (ref "R11") (pin "1") (pinfunction "1_1") (pintype "passive"))
      (node (ref "R14") (pin "2") (pinfunction "2_2") (pintype "passive"))
    )
    (net (code "63") (name "Net-(R11-Pad3)") (class "Default")
      (node (ref "R11") (pin "3") (pinfunction "3_3") (pintype "passive"))
      (node (ref "R13") (pin "2") (pinfunction "2_2") (pintype "passive"))
    )
    (net (code "64") (name "Net-(R12-Pad1)") (class "Default")
      (node (ref "R12") (pin "1") (pinfunction "1_1") (pintype "passive"))
      (node (ref "R16") (pin "2") (pinfunction "2_2") (pintype "passive"))
    )
    (net (code "65") (name "Net-(R12-Pad3)") (class "Default")
      (node (ref "R12") (pin "3") (pinfunction "3_3") (pintype "passive"))
      (node (ref "R15") (pin "2") (pinfunction "2_2") (pintype "passive"))
    )
    (net (code "66") (name "Net-(R17-Pad1)") (class "Default")
      (node (ref "R17") (pin "1") (pinfunction "1_1") (pintype "passive"))
      (node (ref "U5") (pin "1") (pinfunction "Rg_1") (pintype "passive"))
    )
    (net (code "67") (name "Net-(R17-Pad2)") (class "Default")
      (node (ref "R17") (pin "2") (pinfunction "2_2") (pintype "passive"))
      (node (ref "U5") (pin "8") (pinfunction "Rg_8") (pintype "passive"))
    )
    (net (code "68") (name "Net-(R18-Pad1)") (class "Default")
      (node (ref "R18") (pin "1") (pinfunction "1_1") (pintype "passive"))
      (node (ref "U6") (pin "1") (pinfunction "Rg_1") (pintype "passive"))
    )
    (net (code "69") (name "Net-(R18-Pad2)") (class "Default")
      (node (ref "R18") (pin "2") (pinfunction "2_2") (pintype "passive"))
      (node (ref "U6") (pin "8") (pinfunction "Rg_8") (pintype "passive"))
    )
    (net (code "70") (name "Net-(R19-Pad1)") (class "Default")
      (node (ref "R19") (pin "1") (pinfunction "1_1") (pintype "passive"))
      (node (ref "R22") (pin "2") (pinfunction "2_2") (pintype "passive"))
    )
    (net (code "71") (name "Net-(R19-Pad3)") (class "Default")
      (node (ref "R19") (pin "3") (pinfunction "3_3") (pintype "passive"))
      (node (ref "R21") (pin "2") (pinfunction "2_2") (pintype "passive"))
    )
    (net (code "72") (name "Net-(R20-Pad1)") (class "Default")
      (node (ref "R20") (pin "1") (pinfunction "1_1") (pintype "passive"))
      (node (ref "R24") (pin "2") (pinfunction "2_2") (pintype "passive"))
    )
    (net (code "73") (name "Net-(R20-Pad3)") (class "Default")
      (node (ref "R20") (pin "3") (pinfunction "3_3") (pintype "passive"))
      (node (ref "R23") (pin "2") (pinfunction "2_2") (pintype "passive"))
    )
    (net (code "74") (name "Net-(R25-Pad1)") (class "Default")
      (node (ref "R25") (pin "1") (pinfunction "1_1") (pintype "passive"))
      (node (ref "U7") (pin "1") (pinfunction "Rg_1") (pintype "passive"))
    )
    (net (code "75") (name "Net-(R25-Pad2)") (class "Default")
      (node (ref "R25") (pin "2") (pinfunction "2_2") (pintype "passive"))
      (node (ref "U7") (pin "8") (pinfunction "Rg_8") (pintype "passive"))
    )
    (net (code "76") (name "Net-(R26-Pad1)") (class "Default")
      (node (ref "R26") (pin "1") (pinfunction "1_1") (pintype "passive"))
      (node (ref "U8") (pin "1") (pinfunction "Rg_1") (pintype "passive"))
    )
    (net (code "77") (name "Net-(R26-Pad2)") (class "Default")
      (node (ref "R26") (pin "2") (pinfunction "2_2") (pintype "passive"))
      (node (ref "U8") (pin "8") (pinfunction "Rg_8") (pintype "passive"))
    )
    (net (code "78") (name "Net-(R27-Pad1)") (class "Default")
      (node (ref "R27") (pin "1") (pinfunction "1_1") (pintype "passive"))
      (node (ref "R30") (pin "2") (pinfunction "2_2") (pintype "passive"))
    )
    (net (code "79") (name "Net-(R27-Pad3)") (class "Default")
      (node (ref "R27") (pin "3") (pinfunction "3_3") (pintype "passive"))
      (node (ref "R29") (pin "2") (pinfunction "2_2") (pintype "passive"))
    )
    (net (code "80") (name "Net-(R28-Pad1)") (class "Default")
      (node (ref "R28") (pin "1") (pinfunction "1_1") (pintype "passive"))
      (node (ref "R32") (pin "2") (pinfunction "2_2") (pintype "passive"))
    )
    (net (code "81") (name "Net-(R28-Pad3)") (class "Default")
      (node (ref "R28") (pin "3") (pinfunction "3_3") (pintype "passive"))
      (node (ref "R31") (pin "2") (pinfunction "2_2") (pintype "passive"))
    )
    (net (code "82") (name "Net-(R33-Pad1)") (class "Default")
      (node (ref "R33") (pin "1") (pinfunction "1_1") (pintype "passive"))
      (node (ref "U9") (pin "1") (pinfunction "Rg_1") (pintype "passive"))
    )
    (net (code "83") (name "Net-(R33-Pad2)") (class "Default")
      (node (ref "R33") (pin "2") (pinfunction "2_2") (pintype "passive"))
      (node (ref "U9") (pin "8") (pinfunction "Rg_8") (pintype "passive"))
    )
    (net (code "84") (name "Net-(R34-Pad1)") (class "Default")
      (node (ref "R34") (pin "1") (pinfunction "1_1") (pintype "passive"))
      (node (ref "U10") (pin "1") (pinfunction "Rg_1") (pintype "passive"))
    )
    (net (code "85") (name "Net-(R34-Pad2)") (class "Default")
      (node (ref "R34") (pin "2") (pinfunction "2_2") (pintype "passive"))
      (node (ref "U10") (pin "8") (pinfunction "Rg_8") (pintype "passive"))
    )
    (net (code "86") (name "Net-(R35-Pad1)") (class "Default")
      (node (ref "R35") (pin "1") (pinfunction "1_1") (pintype "passive"))
      (node (ref "R38") (pin "2") (pinfunction "2_2") (pintype "passive"))
    )
    (net (code "87") (name "Net-(R35-Pad3)") (class "Default")
      (node (ref "R35") (pin "3") (pinfunction "3_3") (pintype "passive"))
      (node (ref "R37") (pin "2") (pinfunction "2_2") (pintype "passive"))
    )
    (net (code "88") (name "Net-(R36-Pad1)") (class "Default")
      (node (ref "R36") (pin "1") (pinfunction "1_1") (pintype "passive"))
      (node (ref "R40") (pin "2") (pinfunction "2_2") (pintype "passive"))
    )
    (net (code "89") (name "Net-(R36-Pad3)") (class "Default")
      (node (ref "R36") (pin "3") (pinfunction "3_3") (pintype "passive"))
      (node (ref "R39") (pin "2") (pinfunction "2_2") (pintype "passive"))
    )
    (net (code "90") (name "Net-(R41-Pad1)") (class "Default")
      (node (ref "R41") (pin "1") (pinfunction "1_1") (pintype "passive"))
      (node (ref "U11") (pin "1") (pinfunction "Rg_1") (pintype "passive"))
    )
    (net (code "91") (name "Net-(R41-Pad2)") (class "Default")
      (node (ref "R41") (pin "2") (pinfunction "2_2") (pintype "passive"))
      (node (ref "U11") (pin "8") (pinfunction "Rg_8") (pintype "passive"))
    )
    (net (code "92") (name "Net-(R42-Pad1)") (class "Default")
      (node (ref "R42") (pin "1") (pinfunction "1_1") (pintype "passive"))
      (node (ref "U12") (pin "1") (pinfunction "Rg_1") (pintype "passive"))
    )
    (net (code "93") (name "Net-(R42-Pad2)") (class "Default")
      (node (ref "R42") (pin "2") (pinfunction "2_2") (pintype "passive"))
      (node (ref "U12") (pin "8") (pinfunction "Rg_8") (pintype "passive"))
    )
    (net (code "94") (name "Net-(R43-Pad1)") (class "Default")
      (node (ref "R43") (pin "1") (pinfunction "1_1") (pintype "passive"))
      (node (ref "R46") (pin "2") (pinfunction "2_2") (pintype "passive"))
    )
    (net (code "95") (name "Net-(R43-Pad3)") (class "Default")
      (node (ref "R43") (pin "3") (pinfunction "3_3") (pintype "passive"))
      (node (ref "R45") (pin "2") (pinfunction "2_2") (pintype "passive"))
    )
    (net (code "96") (name "Net-(R44-Pad1)") (class "Default")
      (node (ref "R44") (pin "1") (pinfunction "1_1") (pintype "passive"))
      (node (ref "R48") (pin "2") (pinfunction "2_2") (pintype "passive"))
    )
    (net (code "97") (name "Net-(R44-Pad3)") (class "Default")
      (node (ref "R44") (pin "3") (pinfunction "3_3") (pintype "passive"))
      (node (ref "R47") (pin "2") (pinfunction "2_2") (pintype "passive"))
    )
    (net (code "98") (name "Net-(R49-Pad1)") (class "Default")
      (node (ref "R49") (pin "1") (pinfunction "1_1") (pintype "passive"))
      (node (ref "U13") (pin "1") (pinfunction "Rg_1") (pintype "passive"))
    )
    (net (code "99") (name "Net-(R49-Pad2)") (class "Default")
      (node (ref "R49") (pin "2") (pinfunction "2_2") (pintype "passive"))
      (node (ref "U13") (pin "8") (pinfunction "Rg_8") (pintype "passive"))
    )
    (net (code "100") (name "Net-(R50-Pad1)") (class "Default")
      (node (ref "R50") (pin "1") (pinfunction "1_1") (pintype "passive"))
      (node (ref "U14") (pin "1") (pinfunction "Rg_1") (pintype "passive"))
    )
    (net (code "101") (name "Net-(R50-Pad2)") (class "Default")
      (node (ref "R50") (pin "2") (pinfunction "2_2") (pintype "passive"))
      (node (ref "U14") (pin "8") (pinfunction "Rg_8") (pintype "passive"))
    )
    (net (code "102") (name "Net-(R51-Pad1)") (class "Default")
      (node (ref "R51") (pin "1") (pinfunction "1_1") (pintype "passive"))
      (node (ref "R54") (pin "2") (pinfunction "2_2") (pintype "passive"))
    )
    (net (code "103") (name "Net-(R51-Pad3)") (class "Default")
      (node (ref "R51") (pin "3") (pinfunction "3_3") (pintype "passive"))
      (node (ref "R53") (pin "2") (pinfunction "2_2") (pintype "passive"))
    )
    (net (code "104") (name "Net-(R52-Pad1)") (class "Default")
      (node (ref "R52") (pin "1") (pinfunction "1_1") (pintype "passive"))
      (node (ref "R56") (pin "2") (pinfunction "2_2") (pintype "passive"))
    )
    (net (code "105") (name "Net-(R52-Pad3)") (class "Default")
      (node (ref "R52") (pin "3") (pinfunction "3_3") (pintype "passive"))
      (node (ref "R55") (pin "2") (pinfunction "2_2") (pintype "passive"))
    )
    (net (code "106") (name "Net-(R57-Pad1)") (class "Default")
      (node (ref "R57") (pin "1") (pinfunction "1_1") (pintype "passive"))
      (node (ref "U15") (pin "1") (pinfunction "Rg_1") (pintype "passive"))
    )
    (net (code "107") (name "Net-(R57-Pad2)") (class "Default")
      (node (ref "R57") (pin "2") (pinfunction "2_2") (pintype "passive"))
      (node (ref "U15") (pin "8") (pinfunction "Rg_8") (pintype "passive"))
    )
    (net (code "108") (name "Net-(R58-Pad1)") (class "Default")
      (node (ref "R58") (pin "1") (pinfunction "1_1") (pintype "passive"))
      (node (ref "U16") (pin "1") (pinfunction "Rg_1") (pintype "passive"))
    )
    (net (code "109") (name "Net-(R58-Pad2)") (class "Default")
      (node (ref "R58") (pin "2") (pinfunction "2_2") (pintype "passive"))
      (node (ref "U16") (pin "8") (pinfunction "Rg_8") (pintype "passive"))
    )
    (net (code "110") (name "Net-(R59-Pad1)") (class "Default")
      (node (ref "R59") (pin "1") (pinfunction "1_1") (pintype "passive"))
      (node (ref "R62") (pin "2") (pinfunction "2_2") (pintype "passive"))
    )
    (net (code "111") (name "Net-(R59-Pad3)") (class "Default")
      (node (ref "R59") (pin "3") (pinfunction "3_3") (pintype "passive"))
      (node (ref "R61") (pin "2") (pinfunction "2_2") (pintype "passive"))
    )
    (net (code "112") (name "Net-(R60-Pad1)") (class "Default")
      (node (ref "R60") (pin "1") (pinfunction "1_1") (pintype "passive"))
      (node (ref "R64") (pin "2") (pinfunction "2_2") (pintype "passive"))
    )
    (net (code "113") (name "Net-(R60-Pad3)") (class "Default")
      (node (ref "R60") (pin "3") (pinfunction "3_3") (pintype "passive"))
      (node (ref "R63") (pin "2") (pinfunction "2_2") (pintype "passive"))
    )
    (net (code "114") (name "V15+") (class "Default")
      (node (ref "C1") (pin "1") (pinfunction "1_1") (pintype "passive"))
      (node (ref "C10") (pin "1") (pinfunction "1_1") (pintype "passive"))
      (node (ref "C13") (pin "1") (pinfunction "1_1") (pintype "passive"))
      (node (ref "C14") (pin "1") (pinfunction "1_1") (pintype "passive"))
      (node (ref "C17") (pin "1") (pinfunction "1_1") (pintype "passive"))
      (node (ref "C18") (pin "1") (pinfunction "1_1") (pintype "passive"))
      (node (ref "C2") (pin "1") (pinfunction "1_1") (pintype "passive"))
      (node (ref "C21") (pin "1") (pinfunction "1_1") (pintype "passive"))
      (node (ref "C22") (pin "1") (pinfunction "1_1") (pintype "passive"))
      (node (ref "C25") (pin "1") (pinfunction "1_1") (pintype "passive"))
      (node (ref "C26") (pin "1") (pinfunction "1_1") (pintype "passive"))
      (node (ref "C29") (pin "1") (pinfunction "1_1") (pintype "passive"))
      (node (ref "C30") (pin "1") (pinfunction "1_1") (pintype "passive"))
      (node (ref "C5") (pin "1") (pinfunction "1_1") (pintype "passive"))
      (node (ref "C6") (pin "1") (pinfunction "1_1") (pintype "passive"))
      (node (ref "C9") (pin "1") (pinfunction "1_1") (pintype "passive"))
      (node (ref "R14") (pin "1") (pinfunction "1_1") (pintype "passive"))
      (node (ref "R16") (pin "1") (pinfunction "1_1") (pintype "passive"))
      (node (ref "R22") (pin "1") (pinfunction "1_1") (pintype "passive"))
      (node (ref "R24") (pin "1") (pinfunction "1_1") (pintype "passive"))
      (node (ref "R30") (pin "1") (pinfunction "1_1") (pintype "passive"))
      (node (ref "R32") (pin "1") (pinfunction "1_1") (pintype "passive"))
      (node (ref "R38") (pin "1") (pinfunction "1_1") (pintype "passive"))
      (node (ref "R40") (pin "1") (pinfunction "1_1") (pintype "passive"))
      (node (ref "R46") (pin "1") (pinfunction "1_1") (pintype "passive"))
      (node (ref "R48") (pin "1") (pinfunction "1_1") (pintype "passive"))
      (node (ref "R54") (pin "1") (pinfunction "1_1") (pintype "passive"))
      (node (ref "R56") (pin "1") (pinfunction "1_1") (pintype "passive"))
      (node (ref "R6") (pin "1") (pinfunction "1_1") (pintype "passive"))
      (node (ref "R62") (pin "1") (pinfunction "1_1") (pintype "passive"))
      (node (ref "R64") (pin "1") (pinfunction "1_1") (pintype "passive"))
      (node (ref "R8") (pin "1") (pinfunction "1_1") (pintype "passive"))
      (node (ref "U1") (pin "7") (pinfunction "V+_7") (pintype "passive"))
      (node (ref "U10") (pin "7") (pinfunction "V+_7") (pintype "passive"))
      (node (ref "U11") (pin "7") (pinfunction "V+_7") (pintype "passive"))
      (node (ref "U12") (pin "7") (pinfunction "V+_7") (pintype "passive"))
      (node (ref "U13") (pin "7") (pinfunction "V+_7") (pintype "passive"))
      (node (ref "U14") (pin "7") (pinfunction "V+_7") (pintype "passive"))
      (node (ref "U15") (pin "7") (pinfunction "V+_7") (pintype "passive"))
      (node (ref "U16") (pin "7") (pinfunction "V+_7") (pintype "passive"))
      (node (ref "U2") (pin "7") (pinfunction "V+_7") (pintype "passive"))
      (node (ref "U3") (pin "7") (pinfunction "V+_7") (pintype "passive"))
      (node (ref "U4") (pin "7") (pinfunction "V+_7") (pintype "passive"))
      (node (ref "U5") (pin "7") (pinfunction "V+_7") (pintype "passive"))
      (node (ref "U6") (pin "7") (pinfunction "V+_7") (pintype "passive"))
      (node (ref "U7") (pin "7") (pinfunction "V+_7") (pintype "passive"))
      (node (ref "U8") (pin "7") (pinfunction "V+_7") (pintype "passive"))
      (node (ref "U9") (pin "7") (pinfunction "V+_7") (pintype "passive"))
    )
    (net (code "115") (name "V15-") (class "Default")
      (node (ref "C11") (pin "2") (pinfunction "2_2") (pintype "passive"))
      (node (ref "C12") (pin "2") (pinfunction "2_2") (pintype "passive"))
      (node (ref "C15") (pin "2") (pinfunction "2_2") (pintype "passive"))
      (node (ref "C16") (pin "2") (pinfunction "2_2") (pintype "passive"))
      (node (ref "C19") (pin "2") (pinfunction "2_2") (pintype "passive"))
      (node (ref "C20") (pin "2") (pinfunction "2_2") (pintype "passive"))
      (node (ref "C23") (pin "2") (pinfunction "2_2") (pintype "passive"))
      (node (ref "C24") (pin "2") (pinfunction "2_2") (pintype "passive"))
      (node (ref "C27") (pin "2") (pinfunction "2_2") (pintype "passive"))
      (node (ref "C28") (pin "2") (pinfunction "2_2") (pintype "passive"))
      (node (ref "C3") (pin "2") (pinfunction "2_2") (pintype "passive"))
      (node (ref "C31") (pin "2") (pinfunction "2_2") (pintype "passive"))
      (node (ref "C32") (pin "2") (pinfunction "2_2") (pintype "passive"))
      (node (ref "C4") (pin "2") (pinfunction "2_2") (pintype "passive"))
      (node (ref "C7") (pin "2") (pinfunction "2_2") (pintype "passive"))
      (node (ref "C8") (pin "2") (pinfunction "2_2") (pintype "passive"))
      (node (ref "R13") (pin "1") (pinfunction "1_1") (pintype "passive"))
      (node (ref "R15") (pin "1") (pinfunction "1_1") (pintype "passive"))
      (node (ref "R21") (pin "1") (pinfunction "1_1") (pintype "passive"))
      (node (ref "R23") (pin "1") (pinfunction "1_1") (pintype "passive"))
      (node (ref "R29") (pin "1") (pinfunction "1_1") (pintype "passive"))
      (node (ref "R31") (pin "1") (pinfunction "1_1") (pintype "passive"))
      (node (ref "R37") (pin "1") (pinfunction "1_1") (pintype "passive"))
      (node (ref "R39") (pin "1") (pinfunction "1_1") (pintype "passive"))
      (node (ref "R45") (pin "1") (pinfunction "1_1") (pintype "passive"))
      (node (ref "R47") (pin "1") (pinfunction "1_1") (pintype "passive"))
      (node (ref "R5") (pin "1") (pinfunction "1_1") (pintype "passive"))
      (node (ref "R53") (pin "1") (pinfunction "1_1") (pintype "passive"))
      (node (ref "R55") (pin "1") (pinfunction "1_1") (pintype "passive"))
      (node (ref "R61") (pin "1") (pinfunction "1_1") (pintype "passive"))
      (node (ref "R63") (pin "1") (pinfunction "1_1") (pintype "passive"))
      (node (ref "R7") (pin "1") (pinfunction "1_1") (pintype "passive"))
      (node (ref "U1") (pin "4") (pinfunction "V-_4") (pintype "passive"))
      (node (ref "U10") (pin "4") (pinfunction "V-_4") (pintype "passive"))
      (node (ref "U11") (pin "4") (pinfunction "V-_4") (pintype "passive"))
      (node (ref "U12") (pin "4") (pinfunction "V-_4") (pintype "passive"))
      (node (ref "U13") (pin "4") (pinfunction "V-_4") (pintype "passive"))
      (node (ref "U14") (pin "4") (pinfunction "V-_4") (pintype "passive"))
      (node (ref "U15") (pin "4") (pinfunction "V-_4") (pintype "passive"))
      (node (ref "U16") (pin "4") (pinfunction "V-_4") (pintype "passive"))
      (node (ref "U2") (pin "4") (pinfunction "V-_4") (pintype "passive"))
      (node (ref "U3") (pin "4") (pinfunction "V-_4") (pintype "passive"))
      (node (ref "U4") (pin "4") (pinfunction "V-_4") (pintype "passive"))
      (node (ref "U5") (pin "4") (pinfunction "V-_4") (pintype "passive"))
      (node (ref "U6") (pin "4") (pinfunction "V-_4") (pintype "passive"))
      (node (ref "U7") (pin "4") (pinfunction "V-_4") (pintype "passive"))
      (node (ref "U8") (pin "4") (pinfunction "V-_4") (pintype "passive"))
      (node (ref "U9") (pin "4") (pinfunction "V-_4") (pintype "passive"))
    )
  )
)
